# QCopterCAM_CAM_Sch.net
KiCad netlist of a schematic drawn in Altium Designer
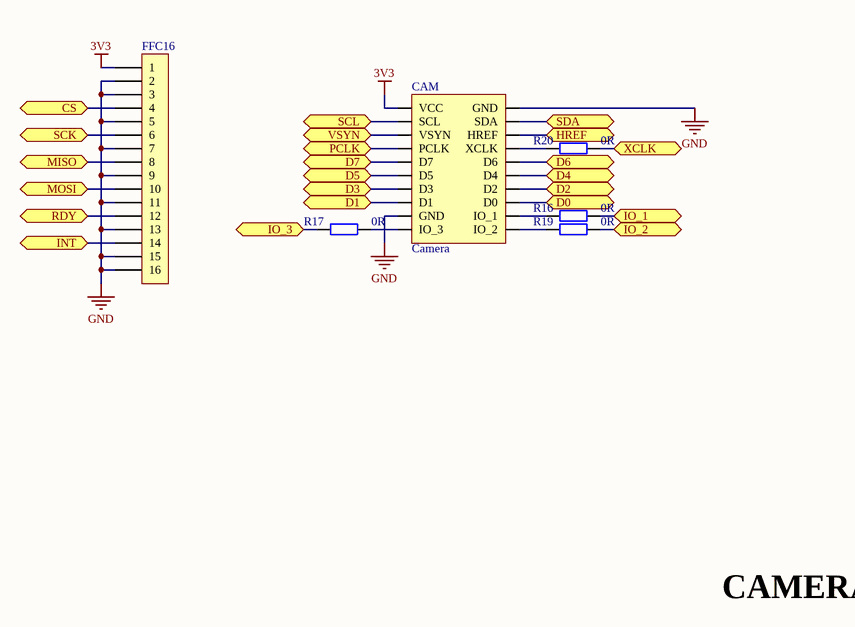
[diagram p0: QCopterCAM_CAM_Sch.SchDoc]

(export (version "E")
  (design (tool "Eeschema 10.0.6"))
  (components
    (comp (ref "CAM")
      (value "Camera")
      (footprint "PCB_Module:CAMERA")
      (description "Module")
      (libsource (lib "SCH_Module") (part "Camera"))
    )
    (comp (ref "FFC16")
      (value "FFC_0.5_16")
      (footprint "PCB_Connector:FFC_0.5_16")
      (description "FFC")
      (libsource (lib "SCH_Connector") (part "FFC_0.5_16"))
    )
    (comp (ref "R16")
      (value "0R")
      (footprint "PCB_Passive:RES_0603")
      (description "Resistor")
      (fields (field (name "Comment") "Res_0603"))
      (libsource (lib "SCH_Passive") (part "Res_0603"))
    )
    (comp (ref "R17")
      (value "0R")
      (footprint "PCB_Passive:RES_0603")
      (description "Resistor")
      (fields (field (name "Comment") "Res_0603"))
      (libsource (lib "SCH_Passive") (part "Res_0603"))
    )
    (comp (ref "R19")
      (value "0R")
      (footprint "PCB_Passive:RES_0603")
      (description "Resistor")
      (fields (field (name "Comment") "Res_0603"))
      (libsource (lib "SCH_Passive") (part "Res_0603"))
    )
    (comp (ref "R20")
      (value "0R")
      (footprint "PCB_Passive:RES_0603")
      (description "Resistor")
      (fields (field (name "Comment") "Res_0603"))
      (libsource (lib "SCH_Passive") (part "Res_0603"))
    )
  )
  (nets
    (net (code "1") (name "/CS") (class "Default")
      (node (ref "FFC16") (pin "4") (pinfunction "4_4") (pintype "passive"))
    )
    (net (code "2") (name "/D0") (class "Default")
      (node (ref "CAM") (pin "16") (pinfunction "D0_16") (pintype "passive"))
    )
    (net (code "3") (name "/D1") (class "Default")
      (node (ref "CAM") (pin "15") (pinfunction "D1_15") (pintype "passive"))
    )
    (net (code "4") (name "/D2") (class "Default")
      (node (ref "CAM") (pin "14") (pinfunction "D2_14") (pintype "passive"))
    )
    (net (code "5") (name "/D3") (class "Default")
      (node (ref "CAM") (pin "13") (pinfunction "D3_13") (pintype "passive"))
    )
    (net (code "6") (name "/D4") (class "Default")
      (node (ref "CAM") (pin "12") (pinfunction "D4_12") (pintype "passive"))
    )
    (net (code "7") (name "/D5") (class "Default")
      (node (ref "CAM") (pin "11") (pinfunction "D5_11") (pintype "passive"))
    )
    (net (code "8") (name "/D6") (class "Default")
      (node (ref "CAM") (pin "10") (pinfunction "D6_10") (pintype "passive"))
    )
    (net (code "9") (name "/D7") (class "Default")
      (node (ref "CAM") (pin "9") (pinfunction "D7_9") (pintype "passive"))
    )
    (net (code "10") (name "/HREF") (class "Default")
      (node (ref "CAM") (pin "6") (pinfunction "HREF_6") (pintype "passive"))
    )
    (net (code "11") (name "/INT") (class "Default")
      (node (ref "FFC16") (pin "14") (pinfunction "14_14") (pintype "passive"))
    )
    (net (code "12") (name "/IO_1") (class "Default")
      (node (ref "R16") (pin "2") (pinfunction "2_2") (pintype "passive"))
    )
    (net (code "13") (name "/IO_2") (class "Default")
      (node (ref "R19") (pin "2") (pinfunction "2_2") (pintype "passive"))
    )
    (net (code "14") (name "/IO_3") (class "Default")
      (node (ref "R17") (pin "1") (pinfunction "1_1") (pintype "passive"))
    )
    (net (code "15") (name "/MISO") (class "Default")
      (node (ref "FFC16") (pin "8") (pinfunction "8_8") (pintype "passive"))
    )
    (net (code "16") (name "/MOSI") (class "Default")
      (node (ref "FFC16") (pin "10") (pinfunction "10_10") (pintype "passive"))
    )
    (net (code "17") (name "/PCLK") (class "Default")
      (node (ref "CAM") (pin "7") (pinfunction "PCLK_7") (pintype "passive"))
    )
    (net (code "18") (name "/RDY") (class "Default")
      (node (ref "FFC16") (pin "12") (pinfunction "12_12") (pintype "passive"))
    )
    (net (code "19") (name "/SCK") (class "Default")
      (node (ref "FFC16") (pin "6") (pinfunction "6_6") (pintype "passive"))
    )
    (net (code "20") (name "/SCL") (class "Default")
      (node (ref "CAM") (pin "3") (pinfunction "SCL_3") (pintype "passive"))
    )
    (net (code "21") (name "/SDA") (class "Default")
      (node (ref "CAM") (pin "4") (pinfunction "SDA_4") (pintype "passive"))
    )
    (net (code "22") (name "/VSYN") (class "Default")
      (node (ref "CAM") (pin "5") (pinfunction "VSYN_5") (pintype "passive"))
    )
    (net (code "23") (name "/XCLK") (class "Default")
      (node (ref "R20") (pin "2") (pinfunction "2_2") (pintype "passive"))
    )
    (net (code "24") (name "3V3") (class "Default")
      (node (ref "CAM") (pin "1") (pinfunction "VCC_1") (pintype "passive"))
      (node (ref "FFC16") (pin "1") (pinfunction "1_1") (pintype "passive"))
    )
    (net (code "25") (name "GND") (class "Default")
      (node (ref "CAM") (pin "17") (pinfunction "GND_17") (pintype "passive"))
      (node (ref "CAM") (pin "2") (pinfunction "GND_2") (pintype "passive"))
      (node (ref "FFC16") (pin "11") (pinfunction "11_11") (pintype "passive"))
      (node (ref "FFC16") (pin "13") (pinfunction "13_13") (pintype "passive"))
      (node (ref "FFC16") (pin "15") (pinfunction "15_15") (pintype "passive"))
      (node (ref "FFC16") (pin "16") (pinfunction "16_16") (pintype "passive"))
      (node (ref "FFC16") (pin "2") (pinfunction "2_2") (pintype "passive"))
      (node (ref "FFC16") (pin "3") (pinfunction "3_3") (pintype "passive"))
      (node (ref "FFC16") (pin "5") (pinfunction "5_5") (pintype "passive"))
      (node (ref "FFC16") (pin "7") (pinfunction "7_7") (pintype "passive"))
      (node (ref "FFC16") (pin "9") (pinfunction "9_9") (pintype "passive"))
    )
    (net (code "26") (name "Net-(CAM-IO_1)") (class "Default")
      (node (ref "CAM") (pin "18") (pinfunction "IO_1_18") (pintype "passive"))
      (node (ref "R16") (pin "1") (pinfunction "1_1") (pintype "passive"))
    )
    (net (code "27") (name "Net-(CAM-IO_2)") (class "Default")
      (node (ref "CAM") (pin "20") (pinfunction "IO_2_20") (pintype "passive"))
      (node (ref "R19") (pin "1") (pinfunction "1_1") (pintype "passive"))
    )
    (net (code "28") (name "Net-(CAM-IO_3)") (class "Default")
      (node (ref "CAM") (pin "19") (pinfunction "IO_3_19") (pintype "passive"))
      (node (ref "R17") (pin "2") (pinfunction "2_2") (pintype "passive"))
    )
    (net (code "29") (name "Net-(CAM-XCLK)") (class "Default")
      (node (ref "CAM") (pin "8") (pinfunction "XCLK_8") (pintype "passive"))
      (node (ref "R20") (pin "1") (pinfunction "1_1") (pintype "passive"))
    )
  )
)
